# TB88_only_Sheet1.net
KiCad netlist of a schematic drawn in Altium Designer
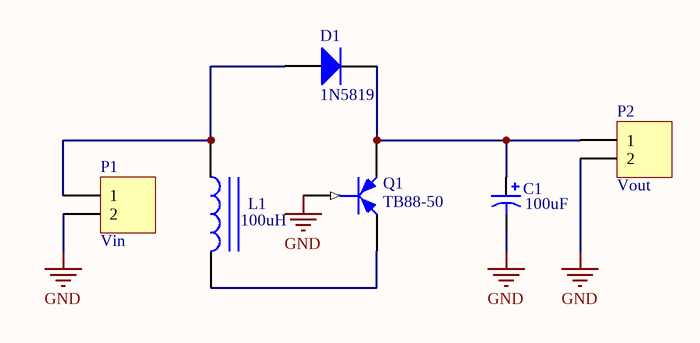
[diagram p0: TB88_only_Sheet1.SchDoc]

(export (version "E")
  (design (tool "Eeschema 10.0.6"))
  (components
    (comp (ref "C1")
      (value "100uF")
      (footprint "CAPPR5-5x5")
      (description "Polarized Capacitor (Radial)")
      (fields (field (name "PUBLISHER") "Altium Limited"))
      (libsource (lib "Miscellaneous Devices") (part "Cap Pol1"))
    )
    (comp (ref "D1")
      (value "1N5819")
      (footprint "DIO10.46-5.3x2.8")
      (description "1 Amp General Purpose Rectifier")
      (fields (field (name "PUBLISHER") "Altium Limited"))
      (libsource (lib "Miscellaneous Devices") (part "Diode 1N4001"))
    )
    (comp (ref "L1")
      (value "100uH")
      (footprint "AXIAL-0.9")
      (description "Magnetic-Core Inductor")
      (fields (field (name "PUBLISHER") "Altium Limited"))
      (libsource (lib "Miscellaneous Devices") (part "Inductor Iron"))
    )
    (comp (ref "P1")
      (value "Vin")
      (footprint "HDR1X2")
      (description "Header, 2-Pin")
      (fields (field (name "PUBLISHER") "Altium Limited"))
      (libsource (lib "Miscellaneous Connectors") (part "Header 2"))
    )
    (comp (ref "P2")
      (value "Vout")
      (footprint "HDR1X2")
      (description "Header, 2-Pin")
      (fields (field (name "PUBLISHER") "Altium Limited"))
      (libsource (lib "Miscellaneous Connectors") (part "Header 2"))
    )
    (comp (ref "Q1")
      (value "TB88-50")
      (footprint "SOT89L")
      (description "DIAC")
      (fields (field (name "PUBLISHER") "Altium Limited"))
      (libsource (lib "Miscellaneous Devices") (part "Diac-PNP"))
    )
  )
  (nets
    (net (code "1") (name "GND") (class "Default")
      (node (ref "C1") (pin "2") (pinfunction "2_2") (pintype "passive"))
      (node (ref "P1") (pin "2") (pinfunction "2_2") (pintype "passive"))
      (node (ref "P2") (pin "2") (pinfunction "2_2") (pintype "passive"))
      (node (ref "Q1") (pin "1") (pinfunction "B_1") (pintype "input"))
    )
    (net (code "2") (name "Net-(D1-A)") (class "Default")
      (node (ref "D1") (pin "1") (pinfunction "A_1") (pintype "passive"))
      (node (ref "L1") (pin "1") (pinfunction "1_1") (pintype "passive"))
      (node (ref "P1") (pin "1") (pinfunction "1_1") (pintype "passive"))
    )
    (net (code "3") (name "Net-(D1-K)") (class "Default")
      (node (ref "C1") (pin "1") (pinfunction "1_1") (pintype "passive"))
      (node (ref "D1") (pin "2") (pinfunction "K_2") (pintype "passive"))
      (node (ref "P2") (pin "1") (pinfunction "1_1") (pintype "passive"))
      (node (ref "Q1") (pin "2") (pinfunction "E_2") (pintype "passive"))
    )
    (net (code "4") (name "Net-(Q1-C)") (class "Default")
      (node (ref "L1") (pin "2") (pinfunction "2_2") (pintype "passive"))
      (node (ref "Q1") (pin "3") (pinfunction "C_3") (pintype "passive"))
    )
  )
)
